# Sheet1.net
KiCad netlist of a schematic drawn in Altium Designer
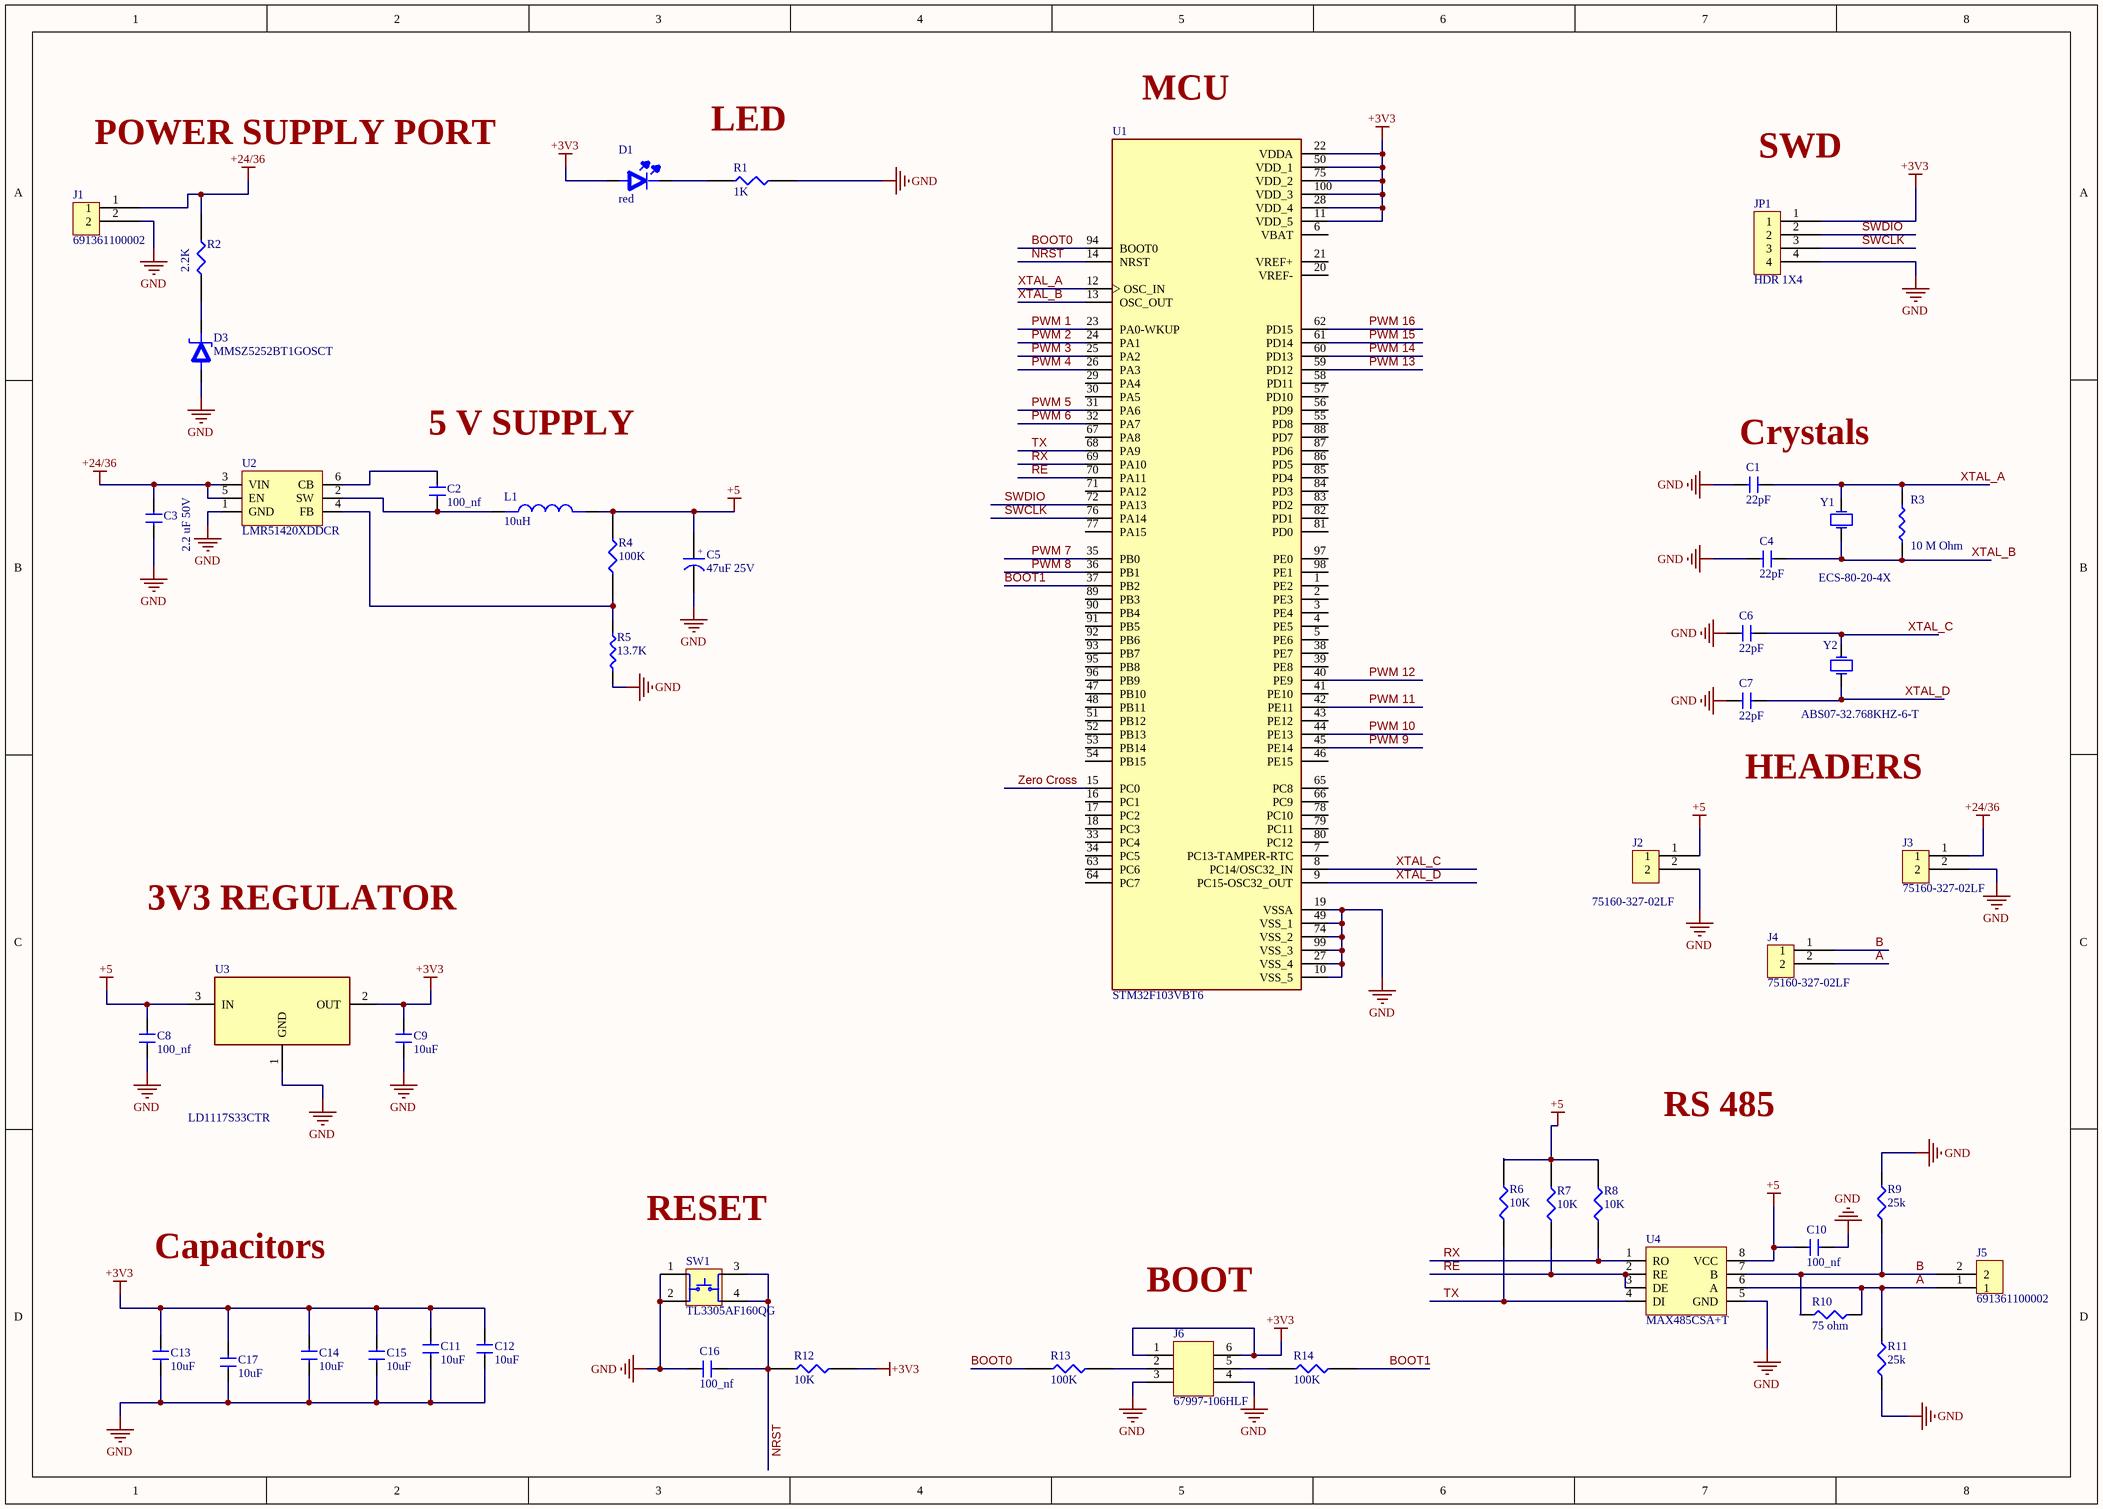
[diagram p0: Sheet1.SchDoc]

(export (version "E")
  (design (tool "Eeschema 10.0.6"))
  (components
    (comp (ref "C1")
      (value "22pF")
      (footprint "CAP_0805")
      (description "Cap Ceramic 22pF 50V C0G 0.25pF SMD 0805 125°C Paper T/R")
      (fields
        (field (name "MANUFACTURER") "KEMET")
        (field (name "MANUFACTURER PART NUMBER") "C0805C220C5GACTU")
      )
      (libsource (lib "STM Schematic Lib") (part "CAP_22pF"))
    )
    (comp (ref "C2")
      (value "100_nf")
      (footprint "CAP_0805")
      (description "Cap Ceramic 0.1uF 50V X7R 10% SMD 0805 125°C Blister Plastic T/R")
      (fields
        (field (name "MANUFACTURER") "TDK")
        (field (name "MANUFACTURER PART NUMBER") "C2012X7R1H104K125AE")
      )
      (libsource (lib "Component Schematic Library V1") (part "CAP_ 0.1uf"))
    )
    (comp (ref "C3")
      (value "2.2 uF 50V")
      (footprint "CAP_0805")
      (description "Cap Ceramic 2.2uF 50V JB 10% SMD 0805 85°C Blister Plastic T/R")
      (fields
        (field (name "MANUFACTURER") "TDK")
        (field (name "MANUFACTURER PART NUMBER") "C2012JB1H225K125AB")
      )
      (libsource (lib "Component Schematic Library V1") (part "cap 2.2 uf 50V 0808"))
    )
    (comp (ref "C4")
      (value "22pF")
      (footprint "CAP_0805")
      (description "Cap Ceramic 22pF 50V C0G 0.25pF SMD 0805 125°C Paper T/R")
      (fields
        (field (name "MANUFACTURER") "KEMET")
        (field (name "MANUFACTURER PART NUMBER") "C0805C220C5GACTU")
      )
      (libsource (lib "STM Schematic Lib") (part "CAP_22pF"))
    )
    (comp (ref "C5")
      (value "47uF 25V")
      (footprint "CAP_ALU_D_Size")
      (description "贴片铝电解电容 47uF ±20% 25V 1000hrs@85°C AEC_D6.3x5.4mm_SM")
      (fields
        (field (name "MANUFACTURER") "Panasonic")
        (field (name "MANUFACTURER PART NUMBER") "EEE-1EA470WP")
      )
      (libsource (lib "Component Schematic Library V1") (part "CAP_POLAR_47uF_25V"))
    )
    (comp (ref "C6")
      (value "22pF")
      (footprint "CAP_0805")
      (description "Cap Ceramic 22pF 50V C0G 0.25pF SMD 0805 125°C Paper T/R")
      (fields
        (field (name "MANUFACTURER") "KEMET")
        (field (name "MANUFACTURER PART NUMBER") "C0805C220C5GACTU")
      )
      (libsource (lib "STM Schematic Lib") (part "CAP_22pF"))
    )
    (comp (ref "C7")
      (value "22pF")
      (footprint "CAP_0805")
      (description "Cap Ceramic 22pF 50V C0G 0.25pF SMD 0805 125°C Paper T/R")
      (fields
        (field (name "MANUFACTURER") "KEMET")
        (field (name "MANUFACTURER PART NUMBER") "C0805C220C5GACTU")
      )
      (libsource (lib "STM Schematic Lib") (part "CAP_22pF"))
    )
    (comp (ref "C8")
      (value "100_nf")
      (footprint "CAP_0805")
      (description "Cap Ceramic 0.1uF 50V X7R 10% SMD 0805 125°C Blister Plastic T/R")
      (fields
        (field (name "MANUFACTURER") "TDK")
        (field (name "MANUFACTURER PART NUMBER") "C2012X7R1H104K125AE")
      )
      (libsource (lib "Component Schematic Library V1") (part "CAP_ 0.1uf"))
    )
    (comp (ref "C9")
      (value "10uF")
      (footprint "CAP_0805")
      (fields
        (field (name "MANUFACTURER") "TDK")
        (field (name "MANUFACTURER PART NUMBER") "C2012X5R1C106M125AC")
        (field (name "TOLERANCE") "20%")
      )
      (libsource (lib "Component Schematic Library V1") (part "CAP_10uF_0805"))
    )
    (comp (ref "C10")
      (value "100_nf")
      (footprint "CAP_0805")
      (description "Cap Ceramic 0.1uF 50V X7R 10% SMD 0805 125°C Blister Plastic T/R")
      (fields
        (field (name "MANUFACTURER") "TDK")
        (field (name "MANUFACTURER PART NUMBER") "C2012X7R1H104K125AE")
      )
      (libsource (lib "Component Schematic Library V1") (part "CAP_ 0.1uf"))
    )
    (comp (ref "C11")
      (value "10uF")
      (footprint "CAP_0805")
      (fields
        (field (name "MANUFACTURER") "TDK")
        (field (name "MANUFACTURER PART NUMBER") "C2012X5R1C106M125AC")
        (field (name "TOLERANCE") "20%")
      )
      (libsource (lib "Component Schematic Library V1") (part "CAP_10uF_0805"))
    )
    (comp (ref "C12")
      (value "10uF")
      (footprint "CAP_0805")
      (fields
        (field (name "MANUFACTURER") "TDK")
        (field (name "MANUFACTURER PART NUMBER") "C2012X5R1C106M125AC")
        (field (name "TOLERANCE") "20%")
      )
      (libsource (lib "Component Schematic Library V1") (part "CAP_10uF_0805"))
    )
    (comp (ref "C13")
      (value "10uF")
      (footprint "CAP_0805")
      (fields
        (field (name "MANUFACTURER") "TDK")
        (field (name "MANUFACTURER PART NUMBER") "C2012X5R1C106M125AC")
        (field (name "TOLERANCE") "20%")
      )
      (libsource (lib "Component Schematic Library V1") (part "CAP_10uF_0805"))
    )
    (comp (ref "C14")
      (value "10uF")
      (footprint "CAP_0805")
      (fields
        (field (name "MANUFACTURER") "TDK")
        (field (name "MANUFACTURER PART NUMBER") "C2012X5R1C106M125AC")
        (field (name "TOLERANCE") "20%")
      )
      (libsource (lib "Component Schematic Library V1") (part "CAP_10uF_0805"))
    )
    (comp (ref "C15")
      (value "10uF")
      (footprint "CAP_0805")
      (fields
        (field (name "MANUFACTURER") "TDK")
        (field (name "MANUFACTURER PART NUMBER") "C2012X5R1C106M125AC")
        (field (name "TOLERANCE") "20%")
      )
      (libsource (lib "Component Schematic Library V1") (part "CAP_10uF_0805"))
    )
    (comp (ref "C16")
      (value "100_nf")
      (footprint "CAP_0805")
      (description "Cap Ceramic 0.1uF 50V X7R 10% SMD 0805 125°C Blister Plastic T/R")
      (fields
        (field (name "MANUFACTURER") "TDK")
        (field (name "MANUFACTURER PART NUMBER") "C2012X7R1H104K125AE")
      )
      (libsource (lib "Component Schematic Library V1") (part "CAP_ 0.1uf"))
    )
    (comp (ref "C17")
      (value "10uF")
      (footprint "CAP_0805")
      (fields
        (field (name "MANUFACTURER") "TDK")
        (field (name "MANUFACTURER PART NUMBER") "C2012X5R1C106M125AC")
        (field (name "TOLERANCE") "20%")
      )
      (libsource (lib "Component Schematic Library V1") (part "CAP_10uF_0805"))
    )
    (comp (ref "D1")
      (value "red")
      (footprint "LED_RED_0805")
      (description "Led SMT Red 0805 Tape")
      (fields
        (field (name "MANUFACTURER") "Osram Opto")
        (field (name "MANUFACTURER PART NUMBER") "LSR976-NR-1")
      )
      (libsource (lib "STM Schematic Lib") (part "LED_RED"))
    )
    (comp (ref "D3")
      (value "MMSZ5252BT1GOSCT")
      (footprint "SOD-123")
      (description "Zener Diode 24 V 500 mW ±5% Surface Mount SOD-123")
      (fields (field (name "MANUFACTURER") "onsemi"))
      (libsource (lib "Component Schematic Library V1") (part "Zener MMSZ5252BT1GOSCT"))
    )
    (comp (ref "J1")
      (value "691361100002")
      (footprint "Screw Terminal 3.5mm")
      (description "3611 Series 3.5mm Pitch Straight Pluggable Term Block; Plug; Cable Mount; 2 Way")
      (fields (field (name "MANUFACTURER") "Wurth Electronics") (field (name "VOLTAGE") "300V"))
      (libsource (lib "") (part "Screw Tarminal 3.5mm pitch_1"))
    )
    (comp (ref "J2")
      (value "75160-327-02LF")
      (footprint "HDR 1x2")
      (description "Conn Unshrouded Header HDR 2 POS 2.54mm Solder ST Thru-Hole Poly Bag")
      (fields (field (name "MANUFACTURER") "Amphenol ICC / FCI"))
      (libsource (lib "Component Schematic Library V1") (part "MALE_HDR_1X2"))
    )
    (comp (ref "J3")
      (value "75160-327-02LF")
      (footprint "HDR 1x2")
      (description "Conn Unshrouded Header HDR 2 POS 2.54mm Solder ST Thru-Hole Poly Bag")
      (fields (field (name "MANUFACTURER") "Amphenol ICC / FCI"))
      (libsource (lib "Component Schematic Library V1") (part "MALE_HDR_1X2"))
    )
    (comp (ref "J4")
      (value "75160-327-02LF")
      (footprint "HDR 1x2")
      (description "Conn Unshrouded Header HDR 2 POS 2.54mm Solder ST Thru-Hole Poly Bag")
      (fields (field (name "MANUFACTURER") "Amphenol ICC / FCI"))
      (libsource (lib "Component Schematic Library V1") (part "MALE_HDR_1X2"))
    )
    (comp (ref "J5")
      (value "691361100002")
      (footprint "Screw Terminal 3.5mm")
      (description "3611 Series 3.5mm Pitch Straight Pluggable Term Block; Plug; Cable Mount; 2 Way")
      (fields (field (name "MANUFACTURER") "Wurth Electronics") (field (name "VOLTAGE") "300V"))
      (libsource (lib "Component Schematic Library V1") (part "Screw Tarminal 3.5mm pitch"))
    )
    (comp (ref "J6")
      (value "67997-106HLF")
      (footprint "MALE_HDR_3X2_2.54mm")
      (description "Conn Unshrouded Header HDR 6 POS 2.54mm Solder ST Top Entry Thru-Hole BergStik® Bulk")
      (fields (field (name "MANUFACTURER") "Amphenol ICC / FCI"))
      (libsource (lib "Component Schematic Library V1") (part "Male_HDR_3X2_2.54mm_Pitch"))
    )
    (comp (ref "JP1")
      (value "HDR 1X4")
      (footprint "HDR 1X4")
      (description "Conn Unshrouded Header HDR 4 POS 2.54mm Solder ST Thru-Hole Bag")
      (fields
        (field (name "MANUFACTURER") "Amphenol ICC")
        (field (name "MANUFACTURER PART NUMBER") "68001-204HLF")
      )
      (libsource (lib "Component Schematic Library V1") (part "MALE_HDR_4X1_Unschrouded"))
    )
    (comp (ref "L1")
      (value "10uH")
      (footprint "B952AS-H-100M=P3")
      (description "Inductor Power Shielded Wirewound 10uH 20% 100KHz Ferrite 2.7A 0.044Ohm DCR 4040 T/R")
      (fields
        (field (name "MANUFACTURER") "Murata")
        (field (name "MANUFACTURER PART NUMBER") "#B952AS-H-100M=P3")
      )
      (libsource (lib "Component Schematic Library V1") (part "Inductor 10uH A"))
    )
    (comp (ref "R1")
      (value "1K")
      (footprint "R_0805")
      (description "贴片电阻 1000Ω ± 1.00% 0.125W ± 100ppm/℃ 0805")
      (fields
        (field (name "MANUFACTURER") "Yageo")
        (field (name "MANUFACTURER PART NUMBER") "RC0805FR-071KL")
      )
      (libsource (lib "Component Schematic Library V1") (part "RES_1_K_0805"))
    )
    (comp (ref "R2")
      (value "2.2K")
      (footprint "R_0805")
      (description "Res High Precision Thin Film 0805 2.2k Ohm 0.1% 1/8W ±15ppm/°C Molded Paper T/R")
      (fields
        (field (name "MANUFACTURER") "Yageo")
        (field (name "MANUFACTURER PART NUMBER") "RT0805BRC072K2L")
      )
      (libsource (lib "Component Schematic Library V1") (part "RES_2.2K 0805"))
    )
    (comp (ref "R3")
      (value "10 M Ohm")
      (footprint "R_0805")
      (description "贴片电阻 10000000Ω ± 1.00% 0.125W ± 100ppm/℃ 0805")
      (fields
        (field (name "MANUFACTURER") "Yageo")
        (field (name "MANUFACTURER PART NUMBER") "RC0805FR-0710ML")
      )
      (libsource (lib "STM Schematic Lib") (part "Res_10 M_Ohm"))
    )
    (comp (ref "R4")
      (value "100K")
      (footprint "R_0805")
      (description "贴片电阻 100000Ω ± 1.00% 0.125W ± 100ppm/℃ 0805")
      (fields
        (field (name "MANUFACTURER") "Yageo")
        (field (name "MANUFACTURER PART NUMBER") "RC0805FR-07100KL")
      )
      (libsource (lib "Component Schematic Library V1") (part "RES_100_K_0805"))
    )
    (comp (ref "R5")
      (value "13.7K")
      (footprint "R_0805")
      (description "Res Thick Film 0805 13.7K Ohm 1% 1/8W ±100ppm/°C SMD Paper T/R")
      (fields
        (field (name "MANUFACTURER") "Yageo")
        (field (name "MANUFACTURER PART NUMBER") "RC0805FR-0713K7L")
      )
      (libsource (lib "Component Schematic Library V1") (part "RES 13.7K 0805"))
    )
    (comp (ref "R6")
      (value "10K")
      (footprint "R_0805")
      (description "贴片电阻 10000Ω ± 1.00% 0.125W ± 100ppm/℃ 0805")
      (fields
        (field (name "MANUFACTURER") "Yageo")
        (field (name "MANUFACTURER PART NUMBER") "RC0805FR-0710KL")
      )
      (libsource (lib "Component Schematic Library V1") (part "RES_10_K_0805"))
    )
    (comp (ref "R7")
      (value "10K")
      (footprint "R_0805")
      (description "贴片电阻 10000Ω ± 1.00% 0.125W ± 100ppm/℃ 0805")
      (fields
        (field (name "MANUFACTURER") "Yageo")
        (field (name "MANUFACTURER PART NUMBER") "RC0805FR-0710KL")
      )
      (libsource (lib "Component Schematic Library V1") (part "RES_10_K_0805"))
    )
    (comp (ref "R8")
      (value "10K")
      (footprint "R_0805")
      (description "贴片电阻 10000Ω ± 1.00% 0.125W ± 100ppm/℃ 0805")
      (fields
        (field (name "MANUFACTURER") "Yageo")
        (field (name "MANUFACTURER PART NUMBER") "RC0805FR-0710KL")
      )
      (libsource (lib "Component Schematic Library V1") (part "RES_10_K_0805"))
    )
    (comp (ref "R9")
      (value "25k")
      (footprint "R_0805")
      (description "Res Thin Film 0805 25K Ohm 0.1% 1/10W ±25ppm/°C Molded SMD SMD Paper T/R")
      (fields
        (field (name "MANUFACTURER") "TE Connectivity")
        (field (name "MANUFACTURER PART NUMBER") "1614911-6")
      )
      (libsource (lib "Component Schematic Library V1") (part "RES 25K 0805"))
    )
    (comp (ref "R10")
      (value "75 ohm")
      (footprint "R_0805")
      (description "Anti-Sulfurated Chip Resistor Automotive Grade Thick Film 0805 75Ohm 5% Paper T/R")
      (fields
        (field (name "MANUFACTURER") "Yageo")
        (field (name "MANUFACTURER PART NUMBER") "AA0805JR-0775RL")
      )
      (libsource (lib "Component Schematic Library V1") (part "Res 75 ohm 0805"))
    )
    (comp (ref "R11")
      (value "25k")
      (footprint "R_0805")
      (description "Res Thin Film 0805 25K Ohm 0.1% 1/10W ±25ppm/°C Molded SMD SMD Paper T/R")
      (fields
        (field (name "MANUFACTURER") "TE Connectivity")
        (field (name "MANUFACTURER PART NUMBER") "1614911-6")
      )
      (libsource (lib "Component Schematic Library V1") (part "RES 25K 0805"))
    )
    (comp (ref "R12")
      (value "10K")
      (footprint "R_0805")
      (description "贴片电阻 10000Ω ± 1.00% 0.125W ± 100ppm/℃ 0805")
      (fields
        (field (name "MANUFACTURER") "Yageo")
        (field (name "MANUFACTURER PART NUMBER") "RC0805FR-0710KL")
      )
      (libsource (lib "Component Schematic Library V1") (part "RES_10_K_0805"))
    )
    (comp (ref "R13")
      (value "100K")
      (footprint "R_0805")
      (description "贴片电阻 100000Ω ± 1.00% 0.125W ± 100ppm/℃ 0805")
      (fields
        (field (name "MANUFACTURER") "Yageo")
        (field (name "MANUFACTURER PART NUMBER") "RC0805FR-07100KL")
      )
      (libsource (lib "Component Schematic Library V1") (part "RES_100_K_0805"))
    )
    (comp (ref "R14")
      (value "100K")
      (footprint "R_0805")
      (description "贴片电阻 100000Ω ± 1.00% 0.125W ± 100ppm/℃ 0805")
      (fields
        (field (name "MANUFACTURER") "Yageo")
        (field (name "MANUFACTURER PART NUMBER") "RC0805FR-07100KL")
      )
      (libsource (lib "Component Schematic Library V1") (part "RES_100_K_0805"))
    )
    (comp (ref "SW1")
      (value "TL3305AF160QG")
      (footprint "SW_PB_SMD")
      (description "TL3305A Series SPST 12 V 4.5 x 4.5 mm 160 gf Top Actuated SMT Tactile Switch")
      (fields (field (name "MANUFACTURER") "E-Switch"))
      (libsource (lib "STM Schematic Lib") (part "SW_PB"))
    )
    (comp (ref "U1")
      (value "STM32F103VBT6")
      (footprint "STM32F103VBT6")
      (description "ARM® Cortex®-M3 STM32 F1 Microcontroller IC 32-Bit 72MHz 128KB (128K x 8) FLASH")
      (fields (field (name "MANUFACTURER") "STMicroelectronics"))
      (libsource (lib "Component Schematic Library V1") (part "STM32F103VBT6"))
    )
    (comp (ref "U2")
      (value "LMR51420XDDCR")
      (footprint "SOT 23-6")
      (fields (field (name "MANUFACTURER") "Texas Instruments"))
      (libsource (lib "Component Schematic Library V1") (part "LMR51420XDDCR"))
    )
    (comp (ref "U3")
      (value "LD1117S33CTR")
      (footprint "SOT 223 3")
      (description "Linear Voltage Regulator IC Positive Fixed 1 Output 3.3V 800mA SOT-223")
      (fields (field (name "MANUFACTURER") "STMicroelectronics"))
      (libsource (lib "Component Schematic Library V1") (part "LDO 3V3"))
    )
    (comp (ref "U4")
      (value "MAX485CSA+T")
      (footprint "8 SOIC")
      (description "1/1 Transceiver Half RS422, RS485 8-SOIC")
      (fields (field (name "MANUFACTURER") "Maxim") (field (name "MANUFACTURER PART NUMBER") "MAX485CSA+"))
      (libsource (lib "Component Schematic Library V1") (part "MAX485CSA+"))
    )
    (comp (ref "Y1")
      (value "ECS-80-20-4X")
      (footprint "XTAL_8_MHZ")
      (description "Crystal 8MHz ±30ppm (Tol) ±50ppm (Stability) 20pF FUND 80Ohm 2-Pin HC-49/USX Thru-Hole Bulk")
      (fields (field (name "MANUFACTURER") "ECS International") (field (name "TOLERANCE") "30ppm"))
      (libsource (lib "STM Schematic Lib") (part "Xtal_8MHZ"))
    )
    (comp (ref "Y2")
      (value "ABS07-32.768KHZ-6-T")
      (footprint "XTAL_32.768 KHZ_SMD")
      (description "Crystal 0.032768MHz ±20ppm (Tol) 6pF Flexural 70000Ohm 2-Pin CSMD T/R")
      (fields (field (name "MANUFACTURER") "Abracon") (field (name "TOLERANCE") "20ppm"))
      (libsource (lib "STM Schematic Lib") (part "XTAl_32.768_KHZ"))
    )
  )
  (nets
    (net (code "1") (name "+3V3") (class "Default")
      (node (ref "C11") (pin "1") (pinfunction "1_1") (pintype "passive"))
      (node (ref "C12") (pin "1") (pinfunction "1_1") (pintype "passive"))
      (node (ref "C13") (pin "1") (pinfunction "1_1") (pintype "passive"))
      (node (ref "C14") (pin "1") (pinfunction "1_1") (pintype "passive"))
      (node (ref "C15") (pin "1") (pinfunction "1_1") (pintype "passive"))
      (node (ref "C17") (pin "1") (pinfunction "1_1") (pintype "passive"))
      (node (ref "C9") (pin "2") (pinfunction "2_2") (pintype "passive"))
      (node (ref "D1") (pin "2") (pinfunction "Anode_2") (pintype "passive"))
      (node (ref "J6") (pin "1") (pinfunction "1_1") (pintype "passive"))
      (node (ref "J6") (pin "6") (pinfunction "6_6") (pintype "passive"))
      (node (ref "JP1") (pin "1") (pinfunction "1_1") (pintype "passive"))
      (node (ref "R12") (pin "2") (pinfunction "3_2") (pintype "passive"))
      (node (ref "U1") (pin "100") (pinfunction "VDD_3_100") (pintype "passive"))
      (node (ref "U1") (pin "11") (pinfunction "VDD_5_11") (pintype "passive"))
      (node (ref "U1") (pin "22") (pinfunction "VDDA_22") (pintype "passive"))
      (node (ref "U1") (pin "28") (pinfunction "VDD_4_28") (pintype "passive"))
      (node (ref "U1") (pin "50") (pinfunction "VDD_1_50") (pintype "passive"))
      (node (ref "U1") (pin "75") (pinfunction "VDD_2_75") (pintype "passive"))
      (node (ref "U3") (pin "2") (pinfunction "OUT_2") (pintype "passive"))
    )
    (net (code "2") (name "+5") (class "Default")
      (node (ref "C10") (pin "1") (pinfunction "1_1") (pintype "passive"))
      (node (ref "C5") (pin "1") (pinfunction "1_1") (pintype "passive"))
      (node (ref "C8") (pin "1") (pinfunction "1_1") (pintype "passive"))
      (node (ref "J2") (pin "1") (pinfunction "1_1") (pintype "passive"))
      (node (ref "L1") (pin "2") (pinfunction "2_2") (pintype "passive"))
      (node (ref "R4") (pin "2") (pinfunction "3_2") (pintype "passive"))
      (node (ref "R6") (pin "1") (pinfunction "2_1") (pintype "passive"))
      (node (ref "R7") (pin "1") (pinfunction "2_1") (pintype "passive"))
      (node (ref "R8") (pin "1") (pinfunction "2_1") (pintype "passive"))
      (node (ref "U3") (pin "3") (pinfunction "IN_3") (pintype "passive"))
      (node (ref "U4") (pin "8") (pinfunction "VCC_8") (pintype "passive"))
    )
    (net (code "3") (name "+24{slash}36") (class "Default")
      (node (ref "C3") (pin "1") (pinfunction "1_1") (pintype "passive"))
      (node (ref "J1") (pin "1") (pinfunction "1_1") (pintype "passive"))
      (node (ref "J3") (pin "1") (pinfunction "1_1") (pintype "passive"))
      (node (ref "R2") (pin "2") (pinfunction "3_2") (pintype "passive"))
      (node (ref "U2") (pin "3") (pinfunction "VIN_3") (pintype "passive"))
      (node (ref "U2") (pin "5") (pinfunction "EN_5") (pintype "passive"))
    )
    (net (code "4") (name "/A") (class "Default")
      (node (ref "J4") (pin "2") (pinfunction "2_2") (pintype "passive"))
      (node (ref "J5") (pin "1") (pinfunction "1_1") (pintype "passive"))
      (node (ref "R10") (pin "2") (pinfunction "3_2") (pintype "passive"))
      (node (ref "R11") (pin "2") (pinfunction "3_2") (pintype "passive"))
      (node (ref "U4") (pin "6") (pinfunction "A_6") (pintype "passive"))
    )
    (net (code "5") (name "/B") (class "Default")
      (node (ref "J4") (pin "1") (pinfunction "1_1") (pintype "passive"))
      (node (ref "J5") (pin "2") (pinfunction "2_2") (pintype "passive"))
      (node (ref "R10") (pin "1") (pinfunction "2_1") (pintype "passive"))
      (node (ref "R9") (pin "1") (pinfunction "2_1") (pintype "passive"))
      (node (ref "U4") (pin "7") (pinfunction "B_7") (pintype "passive"))
    )
    (net (code "6") (name "/BOOT0") (class "Default")
      (node (ref "R13") (pin "1") (pinfunction "2_1") (pintype "passive"))
      (node (ref "U1") (pin "94") (pinfunction "BOOT0_94") (pintype "passive"))
    )
    (net (code "7") (name "/BOOT1") (class "Default")
      (node (ref "R14") (pin "2") (pinfunction "3_2") (pintype "passive"))
      (node (ref "U1") (pin "37") (pinfunction "PB2_37") (pintype "passive"))
    )
    (net (code "8") (name "/NRST") (class "Default")
      (node (ref "C16") (pin "2") (pinfunction "2_2") (pintype "passive"))
      (node (ref "R12") (pin "1") (pinfunction "2_1") (pintype "passive"))
      (node (ref "SW1") (pin "3") (pinfunction "3_3") (pintype "passive"))
      (node (ref "SW1") (pin "4") (pinfunction "4_4") (pintype "passive"))
      (node (ref "U1") (pin "14") (pinfunction "NRST_14") (pintype "passive"))
    )
    (net (code "9") (name "/PWM 1") (class "Default")
      (node (ref "U1") (pin "23") (pinfunction "PA0-WKUP_23") (pintype "passive"))
    )
    (net (code "10") (name "/PWM 2") (class "Default")
      (node (ref "U1") (pin "24") (pinfunction "PA1_24") (pintype "passive"))
    )
    (net (code "11") (name "/PWM 3") (class "Default")
      (node (ref "U1") (pin "25") (pinfunction "PA2_25") (pintype "passive"))
    )
    (net (code "12") (name "/PWM 4") (class "Default")
      (node (ref "U1") (pin "26") (pinfunction "PA3_26") (pintype "passive"))
    )
    (net (code "13") (name "/PWM 5") (class "Default")
      (node (ref "U1") (pin "31") (pinfunction "PA6_31") (pintype "passive"))
    )
    (net (code "14") (name "/PWM 6") (class "Default")
      (node (ref "U1") (pin "32") (pinfunction "PA7_32") (pintype "passive"))
    )
    (net (code "15") (name "/PWM 7") (class "Default")
      (node (ref "U1") (pin "35") (pinfunction "PB0_35") (pintype "passive"))
    )
    (net (code "16") (name "/PWM 8") (class "Default")
      (node (ref "U1") (pin "36") (pinfunction "PB1_36") (pintype "passive"))
    )
    (net (code "17") (name "/PWM 9") (class "Default")
      (node (ref "U1") (pin "45") (pinfunction "PE14_45") (pintype "passive"))
    )
    (net (code "18") (name "/PWM 10") (class "Default")
      (node (ref "U1") (pin "44") (pinfunction "PE13_44") (pintype "passive"))
    )
    (net (code "19") (name "/PWM 11") (class "Default")
      (node (ref "U1") (pin "42") (pinfunction "PE11_42") (pintype "passive"))
    )
    (net (code "20") (name "/PWM 12") (class "Default")
      (node (ref "U1") (pin "40") (pinfunction "PE9_40") (pintype "passive"))
    )
    (net (code "21") (name "/PWM 13") (class "Default")
      (node (ref "U1") (pin "59") (pinfunction "PD12_59") (pintype "passive"))
    )
    (net (code "22") (name "/PWM 14") (class "Default")
      (node (ref "U1") (pin "60") (pinfunction "PD13_60") (pintype "passive"))
    )
    (net (code "23") (name "/PWM 15") (class "Default")
      (node (ref "U1") (pin "61") (pinfunction "PD14_61") (pintype "passive"))
    )
    (net (code "24") (name "/PWM 16") (class "Default")
      (node (ref "U1") (pin "62") (pinfunction "PD15_62") (pintype "passive"))
    )
    (net (code "25") (name "/RE") (class "Default")
      (node (ref "R7") (pin "2") (pinfunction "3_2") (pintype "passive"))
      (node (ref "U1") (pin "70") (pinfunction "PA11_70") (pintype "passive"))
      (node (ref "U4") (pin "2") (pinfunction "RE_2") (pintype "passive"))
      (node (ref "U4") (pin "3") (pinfunction "DE_3") (pintype "passive"))
    )
    (net (code "26") (name "/RX") (class "Default")
      (node (ref "R8") (pin "2") (pinfunction "3_2") (pintype "passive"))
      (node (ref "U1") (pin "69") (pinfunction "PA10_69") (pintype "passive"))
      (node (ref "U4") (pin "1") (pinfunction "RO_1") (pintype "passive"))
    )
    (net (code "27") (name "/SWCLK") (class "Default")
      (node (ref "JP1") (pin "3") (pinfunction "3_3") (pintype "passive"))
      (node (ref "U1") (pin "76") (pinfunction "PA14_76") (pintype "passive"))
    )
    (net (code "28") (name "/SWDIO") (class "Default")
      (node (ref "JP1") (pin "2") (pinfunction "2_2") (pintype "passive"))
      (node (ref "U1") (pin "72") (pinfunction "PA13_72") (pintype "passive"))
    )
    (net (code "29") (name "/TX") (class "Default")
      (node (ref "R6") (pin "2") (pinfunction "3_2") (pintype "passive"))
      (node (ref "U1") (pin "68") (pinfunction "PA9_68") (pintype "passive"))
      (node (ref "U4") (pin "4") (pinfunction "DI_4") (pintype "passive"))
    )
    (net (code "30") (name "/XTAL_A") (class "Default")
      (node (ref "C1") (pin "2") (pinfunction "2_2") (pintype "passive"))
      (node (ref "R3") (pin "1") (pinfunction "1_1") (pintype "passive"))
      (node (ref "U1") (pin "12") (pinfunction "OSC_IN_12") (pintype "passive"))
      (node (ref "Y1") (pin "1") (pinfunction "1_1") (pintype "passive"))
    )
    (net (code "31") (name "/XTAL_B") (class "Default")
      (node (ref "C4") (pin "2") (pinfunction "2_2") (pintype "passive"))
      (node (ref "R3") (pin "2") (pinfunction "2_2") (pintype "passive"))
      (node (ref "U1") (pin "13") (pinfunction "OSC_OUT_13") (pintype "passive"))
      (node (ref "Y1") (pin "2") (pinfunction "2_2") (pintype "passive"))
    )
    (net (code "32") (name "/XTAL_C") (class "Default")
      (node (ref "C6") (pin "2") (pinfunction "2_2") (pintype "passive"))
      (node (ref "U1") (pin "8") (pinfunction "PC14/OSC32_IN_8") (pintype "passive"))
      (node (ref "Y2") (pin "1") (pinfunction "1_1") (pintype "passive"))
    )
    (net (code "33") (name "/XTAL_D") (class "Default")
      (node (ref "C7") (pin "2") (pinfunction "2_2") (pintype "passive"))
      (node (ref "U1") (pin "9") (pinfunction "PC15-OSC32_OUT_9") (pintype "passive"))
      (node (ref "Y2") (pin "2") (pinfunction "2_2") (pintype "passive"))
    )
    (net (code "34") (name "/Zero Cross") (class "Default")
      (node (ref "U1") (pin "15") (pinfunction "PC0_15") (pintype "passive"))
    )
    (net (code "35") (name "GND") (class "Default")
      (node (ref "C1") (pin "1") (pinfunction "1_1") (pintype "passive"))
      (node (ref "C10") (pin "2") (pinfunction "2_2") (pintype "passive"))
      (node (ref "C11") (pin "2") (pinfunction "2_2") (pintype "passive"))
      (node (ref "C12") (pin "2") (pinfunction "2_2") (pintype "passive"))
      (node (ref "C13") (pin "2") (pinfunction "2_2") (pintype "passive"))
      (node (ref "C14") (pin "2") (pinfunction "2_2") (pintype "passive"))
      (node (ref "C15") (pin "2") (pinfunction "2_2") (pintype "passive"))
      (node (ref "C16") (pin "1") (pinfunction "1_1") (pintype "passive"))
      (node (ref "C17") (pin "2") (pinfunction "2_2") (pintype "passive"))
      (node (ref "C3") (pin "2") (pinfunction "2_2") (pintype "passive"))
      (node (ref "C4") (pin "1") (pinfunction "1_1") (pintype "passive"))
      (node (ref "C5") (pin "2") (pinfunction "2_2") (pintype "passive"))
      (node (ref "C6") (pin "1") (pinfunction "1_1") (pintype "passive"))
      (node (ref "C7") (pin "1") (pinfunction "1_1") (pintype "passive"))
      (node (ref "C8") (pin "2") (pinfunction "2_2") (pintype "passive"))
      (node (ref "C9") (pin "1") (pinfunction "1_1") (pintype "passive"))
      (node (ref "D3") (pin "2") (pinfunction "Anode_2") (pintype "passive"))
      (node (ref "J1") (pin "2") (pinfunction "2_2") (pintype "passive"))
      (node (ref "J2") (pin "2") (pinfunction "2_2") (pintype "passive"))
      (node (ref "J3") (pin "2") (pinfunction "2_2") (pintype "passive"))
      (node (ref "J6") (pin "3") (pinfunction "3_3") (pintype "passive"))
      (node (ref "J6") (pin "4") (pinfunction "4_4") (pintype "passive"))
      (node (ref "JP1") (pin "4") (pinfunction "4_4") (pintype "passive"))
      (node (ref "R1") (pin "2") (pinfunction "3_2") (pintype "passive"))
      (node (ref "R11") (pin "1") (pinfunction "2_1") (pintype "passive"))
      (node (ref "R5") (pin "2") (pinfunction "2_2") (pintype "passive"))
      (node (ref "R9") (pin "2") (pinfunction "3_2") (pintype "passive"))
      (node (ref "SW1") (pin "1") (pinfunction "1_1") (pintype "passive"))
      (node (ref "SW1") (pin "2") (pinfunction "2_2") (pintype "passive"))
      (node (ref "U1") (pin "10") (pinfunction "VSS_5_10") (pintype "passive"))
      (node (ref "U1") (pin "19") (pinfunction "VSSA_19") (pintype "passive"))
      (node (ref "U1") (pin "27") (pinfunction "VSS_4_27") (pintype "passive"))
      (node (ref "U1") (pin "49") (pinfunction "VSS_1_49") (pintype "passive"))
      (node (ref "U1") (pin "74") (pinfunction "VSS_2_74") (pintype "passive"))
      (node (ref "U1") (pin "99") (pinfunction "VSS_3_99") (pintype "passive"))
      (node (ref "U2") (pin "1") (pinfunction "GND_1") (pintype "passive"))
      (node (ref "U3") (pin "1") (pinfunction "GND_1") (pintype "passive"))
      (node (ref "U4") (pin "5") (pinfunction "GND_5") (pintype "passive"))
    )
    (net (code "36") (name "Net-(D1-Cathode)") (class "Default")
      (node (ref "D1") (pin "1") (pinfunction "Cathode_1") (pintype "passive"))
      (node (ref "R1") (pin "1") (pinfunction "2_1") (pintype "passive"))
    )
    (net (code "37") (name "Net-(D3-Cathode)") (class "Default")
      (node (ref "D3") (pin "1") (pinfunction "Cathode_1") (pintype "passive"))
      (node (ref "R2") (pin "1") (pinfunction "2_1") (pintype "passive"))
    )
    (net (code "38") (name "Net-(R4-2)") (class "Default")
      (node (ref "R4") (pin "1") (pinfunction "2_1") (pintype "passive"))
      (node (ref "R5") (pin "1") (pinfunction "1_1") (pintype "passive"))
      (node (ref "U2") (pin "4") (pinfunction "FB_4") (pintype "passive"))
    )
    (net (code "39") (name "Net-(R13-3)") (class "Default")
      (node (ref "J6") (pin "2") (pinfunction "2_2") (pintype "passive"))
      (node (ref "R13") (pin "2") (pinfunction "3_2") (pintype "passive"))
    )
    (net (code "40") (name "Net-(R14-2)") (class "Default")
      (node (ref "J6") (pin "5") (pinfunction "5_5") (pintype "passive"))
      (node (ref "R14") (pin "1") (pinfunction "2_1") (pintype "passive"))
    )
    (net (code "41") (name "Net-(U2-CB)") (class "Default")
      (node (ref "C2") (pin "1") (pinfunction "1_1") (pintype "passive"))
      (node (ref "U2") (pin "6") (pinfunction "CB_6") (pintype "passive"))
    )
    (net (code "42") (name "Net-(U2-SW)") (class "Default")
      (node (ref "C2") (pin "2") (pinfunction "2_2") (pintype "passive"))
      (node (ref "L1") (pin "1") (pinfunction "1_1") (pintype "passive"))
      (node (ref "U2") (pin "2") (pinfunction "SW_2") (pintype "passive"))
    )
    (net (code "43") (name "unconnected-(U1-PA4-Pad29)") (class "Default")
      (node (ref "U1") (pin "29") (pinfunction "PA4_29") (pintype "passive"))
    )
    (net (code "44") (name "unconnected-(U1-PA5-Pad30)") (class "Default")
      (node (ref "U1") (pin "30") (pinfunction "PA5_30") (pintype "passive"))
    )
    (net (code "45") (name "unconnected-(U1-PA8-Pad67)") (class "Default")
      (node (ref "U1") (pin "67") (pinfunction "PA8_67") (pintype "passive"))
    )
    (net (code "46") (name "unconnected-(U1-PA12-Pad71)") (class "Default")
      (node (ref "U1") (pin "71") (pinfunction "PA12_71") (pintype "passive"))
    )
    (net (code "47") (name "unconnected-(U1-PA15-Pad77)") (class "Default")
      (node (ref "U1") (pin "77") (pinfunction "PA15_77") (pintype "passive"))
    )
    (net (code "48") (name "unconnected-(U1-PB3-Pad89)") (class "Default")
      (node (ref "U1") (pin "89") (pinfunction "PB3_89") (pintype "passive"))
    )
    (net (code "49") (name "unconnected-(U1-PB4-Pad90)") (class "Default")
      (node (ref "U1") (pin "90") (pinfunction "PB4_90") (pintype "passive"))
    )
    (net (code "50") (name "unconnected-(U1-PB5-Pad91)") (class "Default")
      (node (ref "U1") (pin "91") (pinfunction "PB5_91") (pintype "passive"))
    )
    (net (code "51") (name "unconnected-(U1-PB6-Pad92)") (class "Default")
      (node (ref "U1") (pin "92") (pinfunction "PB6_92") (pintype "passive"))
    )
    (net (code "52") (name "unconnected-(U1-PB7-Pad93)") (class "Default")
      (node (ref "U1") (pin "93") (pinfunction "PB7_93") (pintype "passive"))
    )
    (net (code "53") (name "unconnected-(U1-PB8-Pad95)") (class "Default")
      (node (ref "U1") (pin "95") (pinfunction "PB8_95") (pintype "passive"))
    )
    (net (code "54") (name "unconnected-(U1-PB9-Pad96)") (class "Default")
      (node (ref "U1") (pin "96") (pinfunction "PB9_96") (pintype "passive"))
    )
    (net (code "55") (name "unconnected-(U1-PB10-Pad47)") (class "Default")
      (node (ref "U1") (pin "47") (pinfunction "PB10_47") (pintype "passive"))
    )
    (net (code "56") (name "unconnected-(U1-PB11-Pad48)") (class "Default")
      (node (ref "U1") (pin "48") (pinfunction "PB11_48") (pintype "passive"))
    )
    (net (code "57") (name "unconnected-(U1-PB12-Pad51)") (class "Default")
      (node (ref "U1") (pin "51") (pinfunction "PB12_51") (pintype "passive"))
    )
    (net (code "58") (name "unconnected-(U1-PB13-Pad52)") (class "Default")
      (node (ref "U1") (pin "52") (pinfunction "PB13_52") (pintype "passive"))
    )
    (net (code "59") (name "unconnected-(U1-PB14-Pad53)") (class "Default")
      (node (ref "U1") (pin "53") (pinfunction "PB14_53") (pintype "passive"))
    )
    (net (code "60") (name "unconnected-(U1-PB15-Pad54)") (class "Default")
      (node (ref "U1") (pin "54") (pinfunction "PB15_54") (pintype "passive"))
    )
    (net (code "61") (name "unconnected-(U1-PC1-Pad16)") (class "Default")
      (node (ref "U1") (pin "16") (pinfunction "PC1_16") (pintype "passive"))
    )
    (net (code "62") (name "unconnected-(U1-PC2-Pad17)") (class "Default")
      (node (ref "U1") (pin "17") (pinfunction "PC2_17") (pintype "passive"))
    )
    (net (code "63") (name "unconnected-(U1-PC3-Pad18)") (class "Default")
      (node (ref "U1") (pin "18") (pinfunction "PC3_18") (pintype "passive"))
    )
    (net (code "64") (name "unconnected-(U1-PC4-Pad33)") (class "Default")
      (node (ref "U1") (pin "33") (pinfunction "PC4_33") (pintype "passive"))
    )
    (net (code "65") (name "unconnected-(U1-PC5-Pad34)") (class "Default")
      (node (ref "U1") (pin "34") (pinfunction "PC5_34") (pintype "passive"))
    )
    (net (code "66") (name "unconnected-(U1-PC6-Pad63)") (class "Default")
      (node (ref "U1") (pin "63") (pinfunction "PC6_63") (pintype "passive"))
    )
    (net (code "67") (name "unconnected-(U1-PC7-Pad64)") (class "Default")
      (node (ref "U1") (pin "64") (pinfunction "PC7_64") (pintype "passive"))
    )
    (net (code "68") (name "unconnected-(U1-PC8-Pad65)") (class "Default")
      (node (ref "U1") (pin "65") (pinfunction "PC8_65") (pintype "passive"))
    )
    (net (code "69") (name "unconnected-(U1-PC9-Pad66)") (class "Default")
      (node (ref "U1") (pin "66") (pinfunction "PC9_66") (pintype "passive"))
    )
    (net (code "70") (name "unconnected-(U1-PC10-Pad78)") (class "Default")
      (node (ref "U1") (pin "78") (pinfunction "PC10_78") (pintype "passive"))
    )
    (net (code "71") (name "unconnected-(U1-PC11-Pad79)") (class "Default")
      (node (ref "U1") (pin "79") (pinfunction "PC11_79") (pintype "passive"))
    )
    (net (code "72") (name "unconnected-(U1-PC12-Pad80)") (class "Default")
      (node (ref "U1") (pin "80") (pinfunction "PC12_80") (pintype "passive"))
    )
    (net (code "73") (name "unconnected-(U1-PC13-TAMPER-RTC-Pad7)") (class "Default")
      (node (ref "U1") (pin "7") (pinfunction "PC13-TAMPER-RTC_7") (pintype "passive"))
    )
    (net (code "74") (name "unconnected-(U1-PD0-Pad81)") (class "Default")
      (node (ref "U1") (pin "81") (pinfunction "PD0_81") (pintype "passive"))
    )
    (net (code "75") (name "unconnected-(U1-PD1-Pad82)") (class "Default")
      (node (ref "U1") (pin "82") (pinfunction "PD1_82") (pintype "passive"))
    )
    (net (code "76") (name "unconnected-(U1-PD2-Pad83)") (class "Default")
      (node (ref "U1") (pin "83") (pinfunction "PD2_83") (pintype "passive"))
    )
    (net (code "77") (name "unconnected-(U1-PD3-Pad84)") (class "Default")
      (node (ref "U1") (pin "84") (pinfunction "PD3_84") (pintype "passive"))
    )
    (net (code "78") (name "unconnected-(U1-PD4-Pad85)") (class "Default")
      (node (ref "U1") (pin "85") (pinfunction "PD4_85") (pintype "passive"))
    )
    (net (code "79") (name "unconnected-(U1-PD5-Pad86)") (class "Default")
      (node (ref "U1") (pin "86") (pinfunction "PD5_86") (pintype "passive"))
    )
    (net (code "80") (name "unconnected-(U1-PD6-Pad87)") (class "Default")
      (node (ref "U1") (pin "87") (pinfunction "PD6_87") (pintype "passive"))
    )
    (net (code "81") (name "unconnected-(U1-PD7-Pad88)") (class "Default")
      (node (ref "U1") (pin "88") (pinfunction "PD7_88") (pintype "passive"))
    )
    (net (code "82") (name "unconnected-(U1-PD8-Pad55)") (class "Default")
      (node (ref "U1") (pin "55") (pinfunction "PD8_55") (pintype "passive"))
    )
    (net (code "83") (name "unconnected-(U1-PD9-Pad56)") (class "Default")
      (node (ref "U1") (pin "56") (pinfunction "PD9_56") (pintype "passive"))
    )
    (net (code "84") (name "unconnected-(U1-PD10-Pad57)") (class "Default")
      (node (ref "U1") (pin "57") (pinfunction "PD10_57") (pintype "passive"))
    )
    (net (code "85") (name "unconnected-(U1-PD11-Pad58)") (class "Default")
      (node (ref "U1") (pin "58") (pinfunction "PD11_58") (pintype "passive"))
    )
    (net (code "86") (name "unconnected-(U1-PE0-Pad97)") (class "Default")
      (node (ref "U1") (pin "97") (pinfunction "PE0_97") (pintype "passive"))
    )
    (net (code "87") (name "unconnected-(U1-PE1-Pad98)") (class "Default")
      (node (ref "U1") (pin "98") (pinfunction "PE1_98") (pintype "passive"))
    )
    (net (code "88") (name "unconnected-(U1-PE2-Pad1)") (class "Default")
      (node (ref "U1") (pin "1") (pinfunction "PE2_1") (pintype "passive"))
    )
    (net (code "89") (name "unconnected-(U1-PE3-Pad2)") (class "Default")
      (node (ref "U1") (pin "2") (pinfunction "PE3_2") (pintype "passive"))
    )
    (net (code "90") (name "unconnected-(U1-PE4-Pad3)") (class "Default")
      (node (ref "U1") (pin "3") (pinfunction "PE4_3") (pintype "passive"))
    )
    (net (code "91") (name "unconnected-(U1-PE5-Pad4)") (class "Default")
      (node (ref "U1") (pin "4") (pinfunction "PE5_4") (pintype "passive"))
    )
    (net (code "92") (name "unconnected-(U1-PE6-Pad5)") (class "Default")
      (node (ref "U1") (pin "5") (pinfunction "PE6_5") (pintype "passive"))
    )
    (net (code "93") (name "unconnected-(U1-PE7-Pad38)") (class "Default")
      (node (ref "U1") (pin "38") (pinfunction "PE7_38") (pintype "passive"))
    )
    (net (code "94") (name "unconnected-(U1-PE8-Pad39)") (class "Default")
      (node (ref "U1") (pin "39") (pinfunction "PE8_39") (pintype "passive"))
    )
    (net (code "95") (name "unconnected-(U1-PE10-Pad41)") (class "Default")
      (node (ref "U1") (pin "41") (pinfunction "PE10_41") (pintype "passive"))
    )
    (net (code "96") (name "unconnected-(U1-PE12-Pad43)") (class "Default")
      (node (ref "U1") (pin "43") (pinfunction "PE12_43") (pintype "passive"))
    )
    (net (code "97") (name "unconnected-(U1-PE15-Pad46)") (class "Default")
      (node (ref "U1") (pin "46") (pinfunction "PE15_46") (pintype "passive"))
    )
    (net (code "98") (name "unconnected-(U1-VBAT-Pad6)") (class "Default")
      (node (ref "U1") (pin "6") (pinfunction "VBAT_6") (pintype "passive"))
    )
    (net (code "99") (name "unconnected-(U1-VREF+-Pad21)") (class "Default")
      (node (ref "U1") (pin "21") (pinfunction "VREF+_21") (pintype "passive"))
    )
    (net (code "100") (name "unconnected-(U1-VREF--Pad20)") (class "Default")
      (node (ref "U1") (pin "20") (pinfunction "VREF-_20") (pintype "passive"))
    )
  )
)
